# Backplane_Reference_R2_0.net
KiCad netlist of a schematic drawn in EAGLE
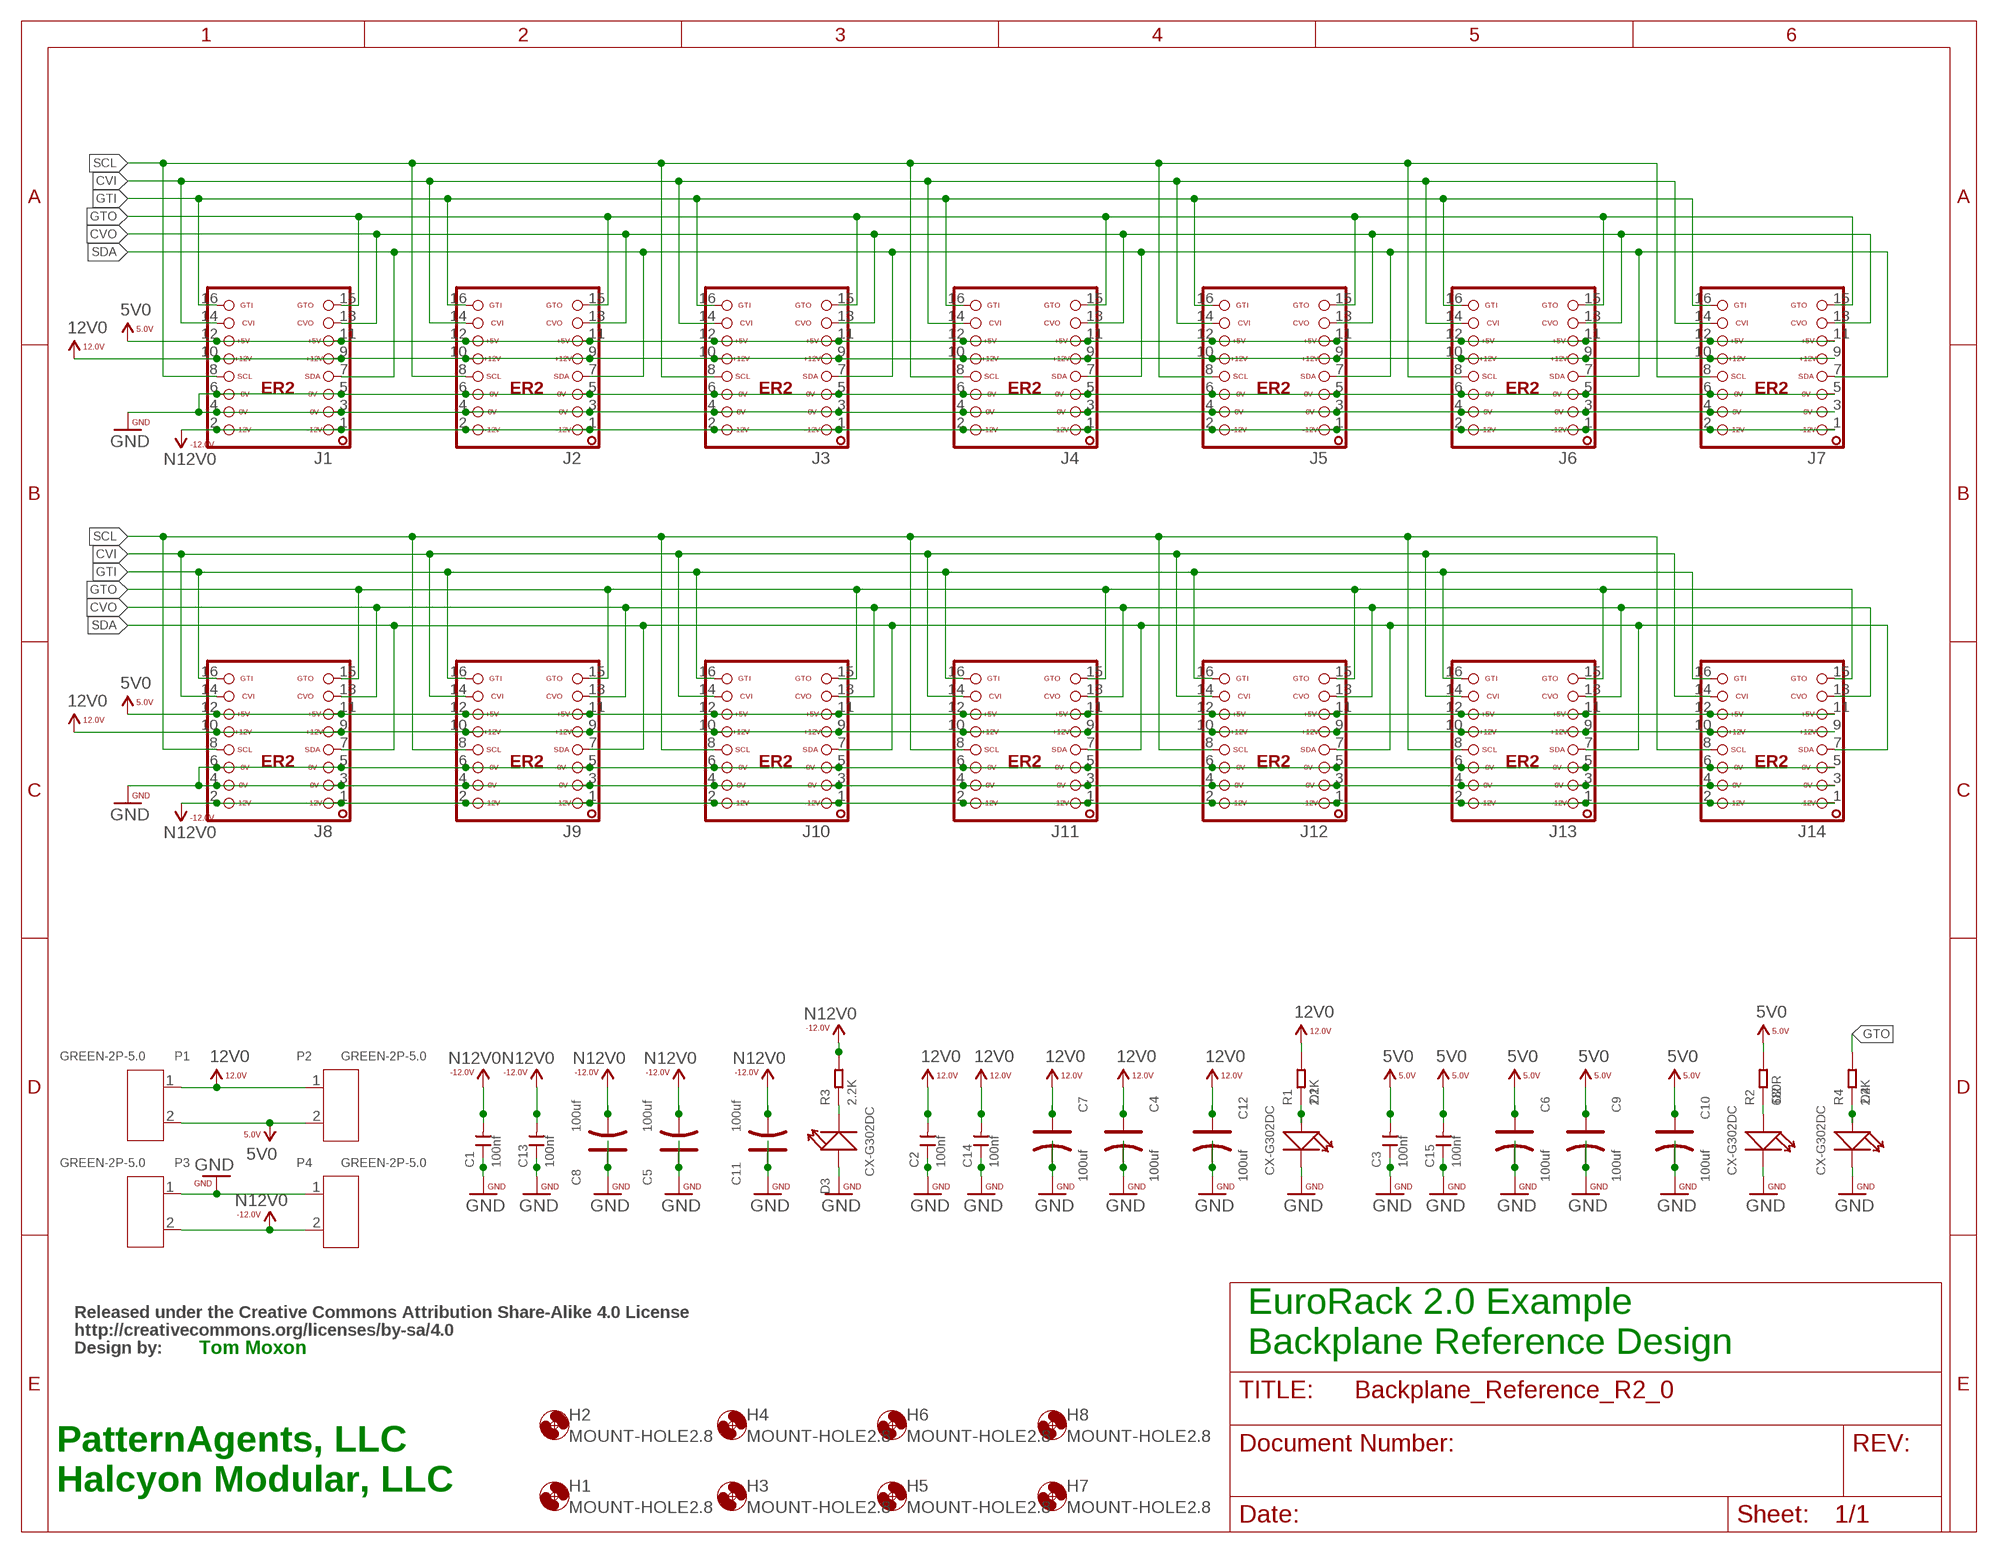
[diagram p0: schematic, sheet 1]

(export (version "E")
  (design (tool "Eeschema 10.0.6"))
  (components
    (comp (ref "C1")
      (value "100nf")
      (footprint "eagle-import:CERAMIC-2.54")
      (fields (field (name "MPN") "CC1-F5SL2A101KSPW"))
      (libsource (lib "eagle-import") (part "DIP-CERAMIC-DISC-100NF-50V-Y5V(D5.0MM)"))
    )
    (comp (ref "C2")
      (value "100nf")
      (footprint "eagle-import:CERAMIC-2.54")
      (fields (field (name "MPN") "CC1-F5SL2A101KSPW"))
      (libsource (lib "eagle-import") (part "DIP-CERAMIC-DISC-100NF-50V-Y5V(D5.0MM)"))
    )
    (comp (ref "C3")
      (value "100nf")
      (footprint "eagle-import:CERAMIC-2.54")
      (fields (field (name "MPN") "CC1-F5SL2A101KSPW"))
      (libsource (lib "eagle-import") (part "DIP-CERAMIC-DISC-100NF-50V-Y5V(D5.0MM)"))
    )
    (comp (ref "C4")
      (value "100uf")
      (footprint "eagle-import:PC-D5.3MM")
      (fields (field (name "MPN") "KS 100uF/16V"))
      (libsource (lib "eagle-import") (part "DIP-ALUMINUM-100UF-16V(D5-H7MM)"))
    )
    (comp (ref "C5")
      (value "100uf")
      (footprint "eagle-import:PC-D5.3MM")
      (fields (field (name "MPN") "KS 100uF/16V"))
      (libsource (lib "eagle-import") (part "DIP-ALUMINUM-100UF-16V(D5-H7MM)"))
    )
    (comp (ref "C6")
      (value "100uf")
      (footprint "eagle-import:PC-D5.3MM")
      (fields (field (name "MPN") "KS 100uF/16V"))
      (libsource (lib "eagle-import") (part "DIP-ALUMINUM-100UF-16V(D5-H7MM)"))
    )
    (comp (ref "C7")
      (value "100uf")
      (footprint "eagle-import:PC-D5.3MM")
      (fields (field (name "MPN") "KS 100uF/16V"))
      (libsource (lib "eagle-import") (part "DIP-ALUMINUM-100UF-16V(D5-H7MM)"))
    )
    (comp (ref "C8")
      (value "100uf")
      (footprint "eagle-import:PC-D5.3MM")
      (fields (field (name "MPN") "KS 100uF/16V"))
      (libsource (lib "eagle-import") (part "DIP-ALUMINUM-100UF-16V(D5-H7MM)"))
    )
    (comp (ref "C9")
      (value "100uf")
      (footprint "eagle-import:PC-D5.3MM")
      (fields (field (name "MPN") "KS 100uF/16V"))
      (libsource (lib "eagle-import") (part "DIP-ALUMINUM-100UF-16V(D5-H7MM)"))
    )
    (comp (ref "C10")
      (value "100uf")
      (footprint "eagle-import:PC-D5.3MM")
      (fields (field (name "MPN") "KS 100uF/16V"))
      (libsource (lib "eagle-import") (part "DIP-ALUMINUM-100UF-16V(D5-H7MM)"))
    )
    (comp (ref "C11")
      (value "100uf")
      (footprint "eagle-import:PC-D5.3MM")
      (fields (field (name "MPN") "KS 100uF/16V"))
      (libsource (lib "eagle-import") (part "DIP-ALUMINUM-100UF-16V(D5-H7MM)"))
    )
    (comp (ref "C12")
      (value "100uf")
      (footprint "eagle-import:PC-D5.3MM")
      (fields (field (name "MPN") "KS 100uF/16V"))
      (libsource (lib "eagle-import") (part "DIP-ALUMINUM-100UF-16V(D5-H7MM)"))
    )
    (comp (ref "C13")
      (value "100nf")
      (footprint "eagle-import:CERAMIC-2.54")
      (fields (field (name "MPN") "CC1-F5SL2A101KSPW"))
      (libsource (lib "eagle-import") (part "DIP-CERAMIC-DISC-100NF-50V-Y5V(D5.0MM)"))
    )
    (comp (ref "C14")
      (value "100nf")
      (footprint "eagle-import:CERAMIC-2.54")
      (fields (field (name "MPN") "CC1-F5SL2A101KSPW"))
      (libsource (lib "eagle-import") (part "DIP-CERAMIC-DISC-100NF-50V-Y5V(D5.0MM)"))
    )
    (comp (ref "C15")
      (value "100nf")
      (footprint "eagle-import:CERAMIC-2.54")
      (fields (field (name "MPN") "CC1-F5SL2A101KSPW"))
      (libsource (lib "eagle-import") (part "DIP-CERAMIC-DISC-100NF-50V-Y5V(D5.0MM)"))
    )
    (comp (ref "D1")
      (value "CX-G302DC")
      (footprint "eagle-import:LED2-2.54-D3.0MM")
      (libsource (lib "eagle-import") (part "DIP-LED-GREEN-GREEN(2P-D3MM)"))
    )
    (comp (ref "D2")
      (value "CX-G302DC")
      (footprint "eagle-import:LED2-2.54-D3.0MM")
      (libsource (lib "eagle-import") (part "DIP-LED-GREEN-GREEN(2P-D3MM)"))
    )
    (comp (ref "D3")
      (value "CX-G302DC")
      (footprint "eagle-import:LED2-2.54-D3.0MM")
      (libsource (lib "eagle-import") (part "DIP-LED-GREEN-GREEN(2P-D3MM)"))
    )
    (comp (ref "D4")
      (value "CX-G302DC")
      (footprint "eagle-import:LED2-2.54-D3.0MM")
      (libsource (lib "eagle-import") (part "DIP-LED-GREEN-GREEN(2P-D3MM)"))
    )
    (comp (ref "H1")
      (value "MOUNT-HOLE2.8")
      (footprint "eagle-import:2,8")
      (libsource (lib "eagle-import") (part "MOUNT-HOLE2.8"))
    )
    (comp (ref "H2")
      (value "MOUNT-HOLE2.8")
      (footprint "eagle-import:2,8")
      (libsource (lib "eagle-import") (part "MOUNT-HOLE2.8"))
    )
    (comp (ref "H3")
      (value "MOUNT-HOLE2.8")
      (footprint "eagle-import:2,8")
      (libsource (lib "eagle-import") (part "MOUNT-HOLE2.8"))
    )
    (comp (ref "H4")
      (value "MOUNT-HOLE2.8")
      (footprint "eagle-import:2,8")
      (libsource (lib "eagle-import") (part "MOUNT-HOLE2.8"))
    )
    (comp (ref "H5")
      (value "MOUNT-HOLE2.8")
      (footprint "eagle-import:2,8")
      (libsource (lib "eagle-import") (part "MOUNT-HOLE2.8"))
    )
    (comp (ref "H6")
      (value "MOUNT-HOLE2.8")
      (footprint "eagle-import:2,8")
      (libsource (lib "eagle-import") (part "MOUNT-HOLE2.8"))
    )
    (comp (ref "H7")
      (value "MOUNT-HOLE2.8")
      (footprint "eagle-import:2,8")
      (libsource (lib "eagle-import") (part "MOUNT-HOLE2.8"))
    )
    (comp (ref "H8")
      (value "MOUNT-HOLE2.8")
      (footprint "eagle-import:2,8")
      (libsource (lib "eagle-import") (part "MOUNT-HOLE2.8"))
    )
    (comp (ref "J1")
      (value "ER2-SHROUD")
      (footprint "eagle-import:ER2")
      (libsource (lib "eagle-import") (part "ER2-SHROUD"))
    )
    (comp (ref "J2")
      (value "ER2-SHROUD")
      (footprint "eagle-import:ER2")
      (libsource (lib "eagle-import") (part "ER2-SHROUD"))
    )
    (comp (ref "J3")
      (value "ER2-SHROUD")
      (footprint "eagle-import:ER2")
      (libsource (lib "eagle-import") (part "ER2-SHROUD"))
    )
    (comp (ref "J4")
      (value "ER2-SHROUD")
      (footprint "eagle-import:ER2")
      (libsource (lib "eagle-import") (part "ER2-SHROUD"))
    )
    (comp (ref "J5")
      (value "ER2-SHROUD")
      (footprint "eagle-import:ER2")
      (libsource (lib "eagle-import") (part "ER2-SHROUD"))
    )
    (comp (ref "J6")
      (value "ER2-SHROUD")
      (footprint "eagle-import:ER2")
      (libsource (lib "eagle-import") (part "ER2-SHROUD"))
    )
    (comp (ref "J7")
      (value "ER2-SHROUD")
      (footprint "eagle-import:ER2")
      (libsource (lib "eagle-import") (part "ER2-SHROUD"))
    )
    (comp (ref "J8")
      (value "ER2-SHROUD")
      (footprint "eagle-import:ER2")
      (libsource (lib "eagle-import") (part "ER2-SHROUD"))
    )
    (comp (ref "J9")
      (value "ER2-SHROUD")
      (footprint "eagle-import:ER2")
      (libsource (lib "eagle-import") (part "ER2-SHROUD"))
    )
    (comp (ref "J10")
      (value "ER2-SHROUD")
      (footprint "eagle-import:ER2")
      (libsource (lib "eagle-import") (part "ER2-SHROUD"))
    )
    (comp (ref "J11")
      (value "ER2-SHROUD")
      (footprint "eagle-import:ER2")
      (libsource (lib "eagle-import") (part "ER2-SHROUD"))
    )
    (comp (ref "J12")
      (value "ER2-SHROUD")
      (footprint "eagle-import:ER2")
      (libsource (lib "eagle-import") (part "ER2-SHROUD"))
    )
    (comp (ref "J13")
      (value "ER2-SHROUD")
      (footprint "eagle-import:ER2")
      (libsource (lib "eagle-import") (part "ER2-SHROUD"))
    )
    (comp (ref "J14")
      (value "ER2-SHROUD")
      (footprint "eagle-import:ER2")
      (libsource (lib "eagle-import") (part "ER2-SHROUD"))
    )
    (comp (ref "P1")
      (value "GREEN-2P-5.0")
      (footprint "eagle-import:H2-5.0-10.5X8.0MM")
      (libsource (lib "eagle-import") (part "SCREW-TERMINAL-GREEN(2P-5.0)"))
    )
    (comp (ref "P2")
      (value "GREEN-2P-5.0")
      (footprint "eagle-import:H2-5.0-10.5X8.0MM")
      (libsource (lib "eagle-import") (part "SCREW-TERMINAL-GREEN(2P-5.0)"))
    )
    (comp (ref "P3")
      (value "GREEN-2P-5.0")
      (footprint "eagle-import:H2-5.0-10.5X8.0MM")
      (libsource (lib "eagle-import") (part "SCREW-TERMINAL-GREEN(2P-5.0)"))
    )
    (comp (ref "P4")
      (value "GREEN-2P-5.0")
      (footprint "eagle-import:H2-5.0-10.5X8.0MM")
      (libsource (lib "eagle-import") (part "SCREW-TERMINAL-GREEN(2P-5.0)"))
    )
    (comp (ref "R1")
      (value "2.2K")
      (footprint "eagle-import:PR-D2.3XL6.5MM")
      (fields (field (name "MPN") "FHCFR-1/4W-222J"))
      (libsource (lib "eagle-import") (part "DIP-RES-2.2K-5%-1/4W(PR-D2.3XL6.5MM)"))
    )
    (comp (ref "R2")
      (value "680R")
      (footprint "eagle-import:PR-D2.3XL6.5MM")
      (fields (field (name "MPN") "FHCFR-1/4W-681J"))
      (libsource (lib "eagle-import") (part "DIP-RES-680R-5%-1/4W(PR-D2.3XL6.5MM)"))
    )
    (comp (ref "R3")
      (value "2.2K")
      (footprint "eagle-import:PR-D2.3XL6.5MM")
      (fields (field (name "MPN") "FHCFR-1/4W-222J"))
      (libsource (lib "eagle-import") (part "DIP-RES-2.2K-5%-1/4W(PR-D2.3XL6.5MM)"))
    )
    (comp (ref "R4")
      (value "2.2K")
      (footprint "eagle-import:PR-D2.3XL6.5MM")
      (fields (field (name "MPN") "FHCFR-1/4W-222J"))
      (libsource (lib "eagle-import") (part "DIP-RES-2.2K-5%-1/4W(PR-D2.3XL6.5MM)"))
    )
    (comp (ref "U$48")
      (value "BY_CC_SA_TEXTTEXT")
      (footprint "eagle-import:BY_CC_SA_TEXT")
      (libsource (lib "eagle-import") (part "BY_CC_SA_TEXTTEXT"))
    )
  )
  (nets
    (net (code "1") (name "5V0") (class "Default")
      (node (ref "C10") (pin "+") (pinfunction "+_+") (pintype "passive"))
      (node (ref "C15") (pin "2") (pinfunction "2_2") (pintype "passive"))
      (node (ref "C3") (pin "2") (pinfunction "2_2") (pintype "passive"))
      (node (ref "C6") (pin "+") (pinfunction "+_+") (pintype "passive"))
      (node (ref "C9") (pin "+") (pinfunction "+_+") (pintype "passive"))
      (node (ref "J1") (pin "11") (pinfunction "11_11") (pintype "passive"))
      (node (ref "J1") (pin "12") (pinfunction "12_12") (pintype "passive"))
      (node (ref "J10") (pin "11") (pinfunction "11_11") (pintype "passive"))
      (node (ref "J10") (pin "12") (pinfunction "12_12") (pintype "passive"))
      (node (ref "J11") (pin "11") (pinfunction "11_11") (pintype "passive"))
      (node (ref "J11") (pin "12") (pinfunction "12_12") (pintype "passive"))
      (node (ref "J12") (pin "11") (pinfunction "11_11") (pintype "passive"))
      (node (ref "J12") (pin "12") (pinfunction "12_12") (pintype "passive"))
      (node (ref "J13") (pin "11") (pinfunction "11_11") (pintype "passive"))
      (node (ref "J13") (pin "12") (pinfunction "12_12") (pintype "passive"))
      (node (ref "J14") (pin "11") (pinfunction "11_11") (pintype "passive"))
      (node (ref "J14") (pin "12") (pinfunction "12_12") (pintype "passive"))
      (node (ref "J2") (pin "11") (pinfunction "11_11") (pintype "passive"))
      (node (ref "J2") (pin "12") (pinfunction "12_12") (pintype "passive"))
      (node (ref "J3") (pin "11") (pinfunction "11_11") (pintype "passive"))
      (node (ref "J3") (pin "12") (pinfunction "12_12") (pintype "passive"))
      (node (ref "J4") (pin "11") (pinfunction "11_11") (pintype "passive"))
      (node (ref "J4") (pin "12") (pinfunction "12_12") (pintype "passive"))
      (node (ref "J5") (pin "11") (pinfunction "11_11") (pintype "passive"))
      (node (ref "J5") (pin "12") (pinfunction "12_12") (pintype "passive"))
      (node (ref "J6") (pin "11") (pinfunction "11_11") (pintype "passive"))
      (node (ref "J6") (pin "12") (pinfunction "12_12") (pintype "passive"))
      (node (ref "J7") (pin "11") (pinfunction "11_11") (pintype "passive"))
      (node (ref "J7") (pin "12") (pinfunction "12_12") (pintype "passive"))
      (node (ref "J8") (pin "11") (pinfunction "11_11") (pintype "passive"))
      (node (ref "J8") (pin "12") (pinfunction "12_12") (pintype "passive"))
      (node (ref "J9") (pin "11") (pinfunction "11_11") (pintype "passive"))
      (node (ref "J9") (pin "12") (pinfunction "12_12") (pintype "passive"))
      (node (ref "P1") (pin "2") (pinfunction "2_2") (pintype "bidirectional"))
      (node (ref "P2") (pin "2") (pinfunction "2_2") (pintype "bidirectional"))
      (node (ref "R2") (pin "2") (pinfunction "2_2") (pintype "passive"))
    )
    (net (code "2") (name "12V0") (class "Default")
      (node (ref "C12") (pin "+") (pinfunction "+_+") (pintype "passive"))
      (node (ref "C14") (pin "2") (pinfunction "2_2") (pintype "passive"))
      (node (ref "C2") (pin "2") (pinfunction "2_2") (pintype "passive"))
      (node (ref "C4") (pin "+") (pinfunction "+_+") (pintype "passive"))
      (node (ref "C7") (pin "+") (pinfunction "+_+") (pintype "passive"))
      (node (ref "J1") (pin "10") (pinfunction "10_10") (pintype "passive"))
      (node (ref "J1") (pin "9") (pinfunction "9_9") (pintype "passive"))
      (node (ref "J10") (pin "10") (pinfunction "10_10") (pintype "passive"))
      (node (ref "J10") (pin "9") (pinfunction "9_9") (pintype "passive"))
      (node (ref "J11") (pin "10") (pinfunction "10_10") (pintype "passive"))
      (node (ref "J11") (pin "9") (pinfunction "9_9") (pintype "passive"))
      (node (ref "J12") (pin "10") (pinfunction "10_10") (pintype "passive"))
      (node (ref "J12") (pin "9") (pinfunction "9_9") (pintype "passive"))
      (node (ref "J13") (pin "10") (pinfunction "10_10") (pintype "passive"))
      (node (ref "J13") (pin "9") (pinfunction "9_9") (pintype "passive"))
      (node (ref "J14") (pin "10") (pinfunction "10_10") (pintype "passive"))
      (node (ref "J14") (pin "9") (pinfunction "9_9") (pintype "passive"))
      (node (ref "J2") (pin "10") (pinfunction "10_10") (pintype "passive"))
      (node (ref "J2") (pin "9") (pinfunction "9_9") (pintype "passive"))
      (node (ref "J3") (pin "10") (pinfunction "10_10") (pintype "passive"))
      (node (ref "J3") (pin "9") (pinfunction "9_9") (pintype "passive"))
      (node (ref "J4") (pin "10") (pinfunction "10_10") (pintype "passive"))
      (node (ref "J4") (pin "9") (pinfunction "9_9") (pintype "passive"))
      (node (ref "J5") (pin "10") (pinfunction "10_10") (pintype "passive"))
      (node (ref "J5") (pin "9") (pinfunction "9_9") (pintype "passive"))
      (node (ref "J6") (pin "10") (pinfunction "10_10") (pintype "passive"))
      (node (ref "J6") (pin "9") (pinfunction "9_9") (pintype "passive"))
      (node (ref "J7") (pin "10") (pinfunction "10_10") (pintype "passive"))
      (node (ref "J7") (pin "9") (pinfunction "9_9") (pintype "passive"))
      (node (ref "J8") (pin "10") (pinfunction "10_10") (pintype "passive"))
      (node (ref "J8") (pin "9") (pinfunction "9_9") (pintype "passive"))
      (node (ref "J9") (pin "10") (pinfunction "10_10") (pintype "passive"))
      (node (ref "J9") (pin "9") (pinfunction "9_9") (pintype "passive"))
      (node (ref "P1") (pin "1") (pinfunction "1_1") (pintype "bidirectional"))
      (node (ref "P2") (pin "1") (pinfunction "1_1") (pintype "bidirectional"))
      (node (ref "R1") (pin "2") (pinfunction "2_2") (pintype "passive"))
    )
    (net (code "3") (name "CVI") (class "Default")
      (node (ref "J1") (pin "14") (pinfunction "14_14") (pintype "passive"))
      (node (ref "J10") (pin "14") (pinfunction "14_14") (pintype "passive"))
      (node (ref "J11") (pin "14") (pinfunction "14_14") (pintype "passive"))
      (node (ref "J12") (pin "14") (pinfunction "14_14") (pintype "passive"))
      (node (ref "J13") (pin "14") (pinfunction "14_14") (pintype "passive"))
      (node (ref "J14") (pin "14") (pinfunction "14_14") (pintype "passive"))
      (node (ref "J2") (pin "14") (pinfunction "14_14") (pintype "passive"))
      (node (ref "J3") (pin "14") (pinfunction "14_14") (pintype "passive"))
      (node (ref "J4") (pin "14") (pinfunction "14_14") (pintype "passive"))
      (node (ref "J5") (pin "14") (pinfunction "14_14") (pintype "passive"))
      (node (ref "J6") (pin "14") (pinfunction "14_14") (pintype "passive"))
      (node (ref "J7") (pin "14") (pinfunction "14_14") (pintype "passive"))
      (node (ref "J8") (pin "14") (pinfunction "14_14") (pintype "passive"))
      (node (ref "J9") (pin "14") (pinfunction "14_14") (pintype "passive"))
    )
    (net (code "4") (name "CVO") (class "Default")
      (node (ref "J1") (pin "13") (pinfunction "13_13") (pintype "passive"))
      (node (ref "J10") (pin "13") (pinfunction "13_13") (pintype "passive"))
      (node (ref "J11") (pin "13") (pinfunction "13_13") (pintype "passive"))
      (node (ref "J12") (pin "13") (pinfunction "13_13") (pintype "passive"))
      (node (ref "J13") (pin "13") (pinfunction "13_13") (pintype "passive"))
      (node (ref "J14") (pin "13") (pinfunction "13_13") (pintype "passive"))
      (node (ref "J2") (pin "13") (pinfunction "13_13") (pintype "passive"))
      (node (ref "J3") (pin "13") (pinfunction "13_13") (pintype "passive"))
      (node (ref "J4") (pin "13") (pinfunction "13_13") (pintype "passive"))
      (node (ref "J5") (pin "13") (pinfunction "13_13") (pintype "passive"))
      (node (ref "J6") (pin "13") (pinfunction "13_13") (pintype "passive"))
      (node (ref "J7") (pin "13") (pinfunction "13_13") (pintype "passive"))
      (node (ref "J8") (pin "13") (pinfunction "13_13") (pintype "passive"))
      (node (ref "J9") (pin "13") (pinfunction "13_13") (pintype "passive"))
    )
    (net (code "5") (name "GND") (class "Default")
      (node (ref "C1") (pin "1") (pinfunction "1_1") (pintype "passive"))
      (node (ref "C10") (pin "-") (pinfunction "-_-") (pintype "passive"))
      (node (ref "C11") (pin "+") (pinfunction "+_+") (pintype "passive"))
      (node (ref "C12") (pin "-") (pinfunction "-_-") (pintype "passive"))
      (node (ref "C13") (pin "1") (pinfunction "1_1") (pintype "passive"))
      (node (ref "C14") (pin "1") (pinfunction "1_1") (pintype "passive"))
      (node (ref "C15") (pin "1") (pinfunction "1_1") (pintype "passive"))
      (node (ref "C2") (pin "1") (pinfunction "1_1") (pintype "passive"))
      (node (ref "C3") (pin "1") (pinfunction "1_1") (pintype "passive"))
      (node (ref "C4") (pin "-") (pinfunction "-_-") (pintype "passive"))
      (node (ref "C5") (pin "+") (pinfunction "+_+") (pintype "passive"))
      (node (ref "C6") (pin "-") (pinfunction "-_-") (pintype "passive"))
      (node (ref "C7") (pin "-") (pinfunction "-_-") (pintype "passive"))
      (node (ref "C8") (pin "+") (pinfunction "+_+") (pintype "passive"))
      (node (ref "C9") (pin "-") (pinfunction "-_-") (pintype "passive"))
      (node (ref "D1") (pin "K") (pinfunction "-_K") (pintype "passive"))
      (node (ref "D2") (pin "K") (pinfunction "-_K") (pintype "passive"))
      (node (ref "D3") (pin "A") (pinfunction "+_A") (pintype "passive"))
      (node (ref "D4") (pin "K") (pinfunction "-_K") (pintype "passive"))
      (node (ref "J1") (pin "3") (pinfunction "3_3") (pintype "passive"))
      (node (ref "J1") (pin "4") (pinfunction "4_4") (pintype "passive"))
      (node (ref "J1") (pin "5") (pinfunction "5_5") (pintype "passive"))
      (node (ref "J1") (pin "6") (pinfunction "6_6") (pintype "passive"))
      (node (ref "J10") (pin "3") (pinfunction "3_3") (pintype "passive"))
      (node (ref "J10") (pin "4") (pinfunction "4_4") (pintype "passive"))
      (node (ref "J10") (pin "5") (pinfunction "5_5") (pintype "passive"))
      (node (ref "J10") (pin "6") (pinfunction "6_6") (pintype "passive"))
      (node (ref "J11") (pin "3") (pinfunction "3_3") (pintype "passive"))
      (node (ref "J11") (pin "4") (pinfunction "4_4") (pintype "passive"))
      (node (ref "J11") (pin "5") (pinfunction "5_5") (pintype "passive"))
      (node (ref "J11") (pin "6") (pinfunction "6_6") (pintype "passive"))
      (node (ref "J12") (pin "3") (pinfunction "3_3") (pintype "passive"))
      (node (ref "J12") (pin "4") (pinfunction "4_4") (pintype "passive"))
      (node (ref "J12") (pin "5") (pinfunction "5_5") (pintype "passive"))
      (node (ref "J12") (pin "6") (pinfunction "6_6") (pintype "passive"))
      (node (ref "J13") (pin "3") (pinfunction "3_3") (pintype "passive"))
      (node (ref "J13") (pin "4") (pinfunction "4_4") (pintype "passive"))
      (node (ref "J13") (pin "5") (pinfunction "5_5") (pintype "passive"))
      (node (ref "J13") (pin "6") (pinfunction "6_6") (pintype "passive"))
      (node (ref "J14") (pin "3") (pinfunction "3_3") (pintype "passive"))
      (node (ref "J14") (pin "4") (pinfunction "4_4") (pintype "passive"))
      (node (ref "J14") (pin "5") (pinfunction "5_5") (pintype "passive"))
      (node (ref "J14") (pin "6") (pinfunction "6_6") (pintype "passive"))
      (node (ref "J2") (pin "3") (pinfunction "3_3") (pintype "passive"))
      (node (ref "J2") (pin "4") (pinfunction "4_4") (pintype "passive"))
      (node (ref "J2") (pin "5") (pinfunction "5_5") (pintype "passive"))
      (node (ref "J2") (pin "6") (pinfunction "6_6") (pintype "passive"))
      (node (ref "J3") (pin "3") (pinfunction "3_3") (pintype "passive"))
      (node (ref "J3") (pin "4") (pinfunction "4_4") (pintype "passive"))
      (node (ref "J3") (pin "5") (pinfunction "5_5") (pintype "passive"))
      (node (ref "J3") (pin "6") (pinfunction "6_6") (pintype "passive"))
      (node (ref "J4") (pin "3") (pinfunction "3_3") (pintype "passive"))
      (node (ref "J4") (pin "4") (pinfunction "4_4") (pintype "passive"))
      (node (ref "J4") (pin "5") (pinfunction "5_5") (pintype "passive"))
      (node (ref "J4") (pin "6") (pinfunction "6_6") (pintype "passive"))
      (node (ref "J5") (pin "3") (pinfunction "3_3") (pintype "passive"))
      (node (ref "J5") (pin "4") (pinfunction "4_4") (pintype "passive"))
      (node (ref "J5") (pin "5") (pinfunction "5_5") (pintype "passive"))
      (node (ref "J5") (pin "6") (pinfunction "6_6") (pintype "passive"))
      (node (ref "J6") (pin "3") (pinfunction "3_3") (pintype "passive"))
      (node (ref "J6") (pin "4") (pinfunction "4_4") (pintype "passive"))
      (node (ref "J6") (pin "5") (pinfunction "5_5") (pintype "passive"))
      (node (ref "J6") (pin "6") (pinfunction "6_6") (pintype "passive"))
      (node (ref "J7") (pin "3") (pinfunction "3_3") (pintype "passive"))
      (node (ref "J7") (pin "4") (pinfunction "4_4") (pintype "passive"))
      (node (ref "J7") (pin "5") (pinfunction "5_5") (pintype "passive"))
      (node (ref "J7") (pin "6") (pinfunction "6_6") (pintype "passive"))
      (node (ref "J8") (pin "3") (pinfunction "3_3") (pintype "passive"))
      (node (ref "J8") (pin "4") (pinfunction "4_4") (pintype "passive"))
      (node (ref "J8") (pin "5") (pinfunction "5_5") (pintype "passive"))
      (node (ref "J8") (pin "6") (pinfunction "6_6") (pintype "passive"))
      (node (ref "J9") (pin "3") (pinfunction "3_3") (pintype "passive"))
      (node (ref "J9") (pin "4") (pinfunction "4_4") (pintype "passive"))
      (node (ref "J9") (pin "5") (pinfunction "5_5") (pintype "passive"))
      (node (ref "J9") (pin "6") (pinfunction "6_6") (pintype "passive"))
      (node (ref "P3") (pin "1") (pinfunction "1_1") (pintype "bidirectional"))
      (node (ref "P4") (pin "1") (pinfunction "1_1") (pintype "bidirectional"))
    )
    (net (code "6") (name "GTI") (class "Default")
      (node (ref "J1") (pin "16") (pinfunction "16_16") (pintype "passive"))
      (node (ref "J10") (pin "16") (pinfunction "16_16") (pintype "passive"))
      (node (ref "J11") (pin "16") (pinfunction "16_16") (pintype "passive"))
      (node (ref "J12") (pin "16") (pinfunction "16_16") (pintype "passive"))
      (node (ref "J13") (pin "16") (pinfunction "16_16") (pintype "passive"))
      (node (ref "J14") (pin "16") (pinfunction "16_16") (pintype "passive"))
      (node (ref "J2") (pin "16") (pinfunction "16_16") (pintype "passive"))
      (node (ref "J3") (pin "16") (pinfunction "16_16") (pintype "passive"))
      (node (ref "J4") (pin "16") (pinfunction "16_16") (pintype "passive"))
      (node (ref "J5") (pin "16") (pinfunction "16_16") (pintype "passive"))
      (node (ref "J6") (pin "16") (pinfunction "16_16") (pintype "passive"))
      (node (ref "J7") (pin "16") (pinfunction "16_16") (pintype "passive"))
      (node (ref "J8") (pin "16") (pinfunction "16_16") (pintype "passive"))
      (node (ref "J9") (pin "16") (pinfunction "16_16") (pintype "passive"))
    )
    (net (code "7") (name "GTO") (class "Default")
      (node (ref "J1") (pin "15") (pinfunction "15_15") (pintype "passive"))
      (node (ref "J10") (pin "15") (pinfunction "15_15") (pintype "passive"))
      (node (ref "J11") (pin "15") (pinfunction "15_15") (pintype "passive"))
      (node (ref "J12") (pin "15") (pinfunction "15_15") (pintype "passive"))
      (node (ref "J13") (pin "15") (pinfunction "15_15") (pintype "passive"))
      (node (ref "J14") (pin "15") (pinfunction "15_15") (pintype "passive"))
      (node (ref "J2") (pin "15") (pinfunction "15_15") (pintype "passive"))
      (node (ref "J3") (pin "15") (pinfunction "15_15") (pintype "passive"))
      (node (ref "J4") (pin "15") (pinfunction "15_15") (pintype "passive"))
      (node (ref "J5") (pin "15") (pinfunction "15_15") (pintype "passive"))
      (node (ref "J6") (pin "15") (pinfunction "15_15") (pintype "passive"))
      (node (ref "J7") (pin "15") (pinfunction "15_15") (pintype "passive"))
      (node (ref "J8") (pin "15") (pinfunction "15_15") (pintype "passive"))
      (node (ref "J9") (pin "15") (pinfunction "15_15") (pintype "passive"))
      (node (ref "R4") (pin "2") (pinfunction "2_2") (pintype "passive"))
    )
    (net (code "8") (name "N12V0") (class "Default")
      (node (ref "C1") (pin "2") (pinfunction "2_2") (pintype "passive"))
      (node (ref "C11") (pin "-") (pinfunction "-_-") (pintype "passive"))
      (node (ref "C13") (pin "2") (pinfunction "2_2") (pintype "passive"))
      (node (ref "C5") (pin "-") (pinfunction "-_-") (pintype "passive"))
      (node (ref "C8") (pin "-") (pinfunction "-_-") (pintype "passive"))
      (node (ref "J1") (pin "1") (pinfunction "1_1") (pintype "passive"))
      (node (ref "J1") (pin "2") (pinfunction "2_2") (pintype "passive"))
      (node (ref "J10") (pin "1") (pinfunction "1_1") (pintype "passive"))
      (node (ref "J10") (pin "2") (pinfunction "2_2") (pintype "passive"))
      (node (ref "J11") (pin "1") (pinfunction "1_1") (pintype "passive"))
      (node (ref "J11") (pin "2") (pinfunction "2_2") (pintype "passive"))
      (node (ref "J12") (pin "1") (pinfunction "1_1") (pintype "passive"))
      (node (ref "J12") (pin "2") (pinfunction "2_2") (pintype "passive"))
      (node (ref "J13") (pin "1") (pinfunction "1_1") (pintype "passive"))
      (node (ref "J13") (pin "2") (pinfunction "2_2") (pintype "passive"))
      (node (ref "J14") (pin "1") (pinfunction "1_1") (pintype "passive"))
      (node (ref "J14") (pin "2") (pinfunction "2_2") (pintype "passive"))
      (node (ref "J2") (pin "1") (pinfunction "1_1") (pintype "passive"))
      (node (ref "J2") (pin "2") (pinfunction "2_2") (pintype "passive"))
      (node (ref "J3") (pin "1") (pinfunction "1_1") (pintype "passive"))
      (node (ref "J3") (pin "2") (pinfunction "2_2") (pintype "passive"))
      (node (ref "J4") (pin "1") (pinfunction "1_1") (pintype "passive"))
      (node (ref "J4") (pin "2") (pinfunction "2_2") (pintype "passive"))
      (node (ref "J5") (pin "1") (pinfunction "1_1") (pintype "passive"))
      (node (ref "J5") (pin "2") (pinfunction "2_2") (pintype "passive"))
      (node (ref "J6") (pin "1") (pinfunction "1_1") (pintype "passive"))
      (node (ref "J6") (pin "2") (pinfunction "2_2") (pintype "passive"))
      (node (ref "J7") (pin "1") (pinfunction "1_1") (pintype "passive"))
      (node (ref "J7") (pin "2") (pinfunction "2_2") (pintype "passive"))
      (node (ref "J8") (pin "1") (pinfunction "1_1") (pintype "passive"))
      (node (ref "J8") (pin "2") (pinfunction "2_2") (pintype "passive"))
      (node (ref "J9") (pin "1") (pinfunction "1_1") (pintype "passive"))
      (node (ref "J9") (pin "2") (pinfunction "2_2") (pintype "passive"))
      (node (ref "P3") (pin "2") (pinfunction "2_2") (pintype "bidirectional"))
      (node (ref "P4") (pin "2") (pinfunction "2_2") (pintype "bidirectional"))
      (node (ref "R3") (pin "2") (pinfunction "2_2") (pintype "passive"))
    )
    (net (code "9") (name "Net-(D1-+)") (class "Default")
      (node (ref "D1") (pin "A") (pinfunction "+_A") (pintype "passive"))
      (node (ref "R1") (pin "1") (pinfunction "1_1") (pintype "passive"))
    )
    (net (code "10") (name "Net-(D2-+)") (class "Default")
      (node (ref "D2") (pin "A") (pinfunction "+_A") (pintype "passive"))
      (node (ref "R2") (pin "1") (pinfunction "1_1") (pintype "passive"))
    )
    (net (code "11") (name "Net-(D3--)") (class "Default")
      (node (ref "D3") (pin "K") (pinfunction "-_K") (pintype "passive"))
      (node (ref "R3") (pin "1") (pinfunction "1_1") (pintype "passive"))
    )
    (net (code "12") (name "Net-(D4-+)") (class "Default")
      (node (ref "D4") (pin "A") (pinfunction "+_A") (pintype "passive"))
      (node (ref "R4") (pin "1") (pinfunction "1_1") (pintype "passive"))
    )
    (net (code "13") (name "SCL") (class "Default")
      (node (ref "J1") (pin "8") (pinfunction "8_8") (pintype "passive"))
      (node (ref "J10") (pin "8") (pinfunction "8_8") (pintype "passive"))
      (node (ref "J11") (pin "8") (pinfunction "8_8") (pintype "passive"))
      (node (ref "J12") (pin "8") (pinfunction "8_8") (pintype "passive"))
      (node (ref "J13") (pin "8") (pinfunction "8_8") (pintype "passive"))
      (node (ref "J14") (pin "8") (pinfunction "8_8") (pintype "passive"))
      (node (ref "J2") (pin "8") (pinfunction "8_8") (pintype "passive"))
      (node (ref "J3") (pin "8") (pinfunction "8_8") (pintype "passive"))
      (node (ref "J4") (pin "8") (pinfunction "8_8") (pintype "passive"))
      (node (ref "J5") (pin "8") (pinfunction "8_8") (pintype "passive"))
      (node (ref "J6") (pin "8") (pinfunction "8_8") (pintype "passive"))
      (node (ref "J7") (pin "8") (pinfunction "8_8") (pintype "passive"))
      (node (ref "J8") (pin "8") (pinfunction "8_8") (pintype "passive"))
      (node (ref "J9") (pin "8") (pinfunction "8_8") (pintype "passive"))
    )
    (net (code "14") (name "SDA") (class "Default")
      (node (ref "J1") (pin "7") (pinfunction "7_7") (pintype "passive"))
      (node (ref "J10") (pin "7") (pinfunction "7_7") (pintype "passive"))
      (node (ref "J11") (pin "7") (pinfunction "7_7") (pintype "passive"))
      (node (ref "J12") (pin "7") (pinfunction "7_7") (pintype "passive"))
      (node (ref "J13") (pin "7") (pinfunction "7_7") (pintype "passive"))
      (node (ref "J14") (pin "7") (pinfunction "7_7") (pintype "passive"))
      (node (ref "J2") (pin "7") (pinfunction "7_7") (pintype "passive"))
      (node (ref "J3") (pin "7") (pinfunction "7_7") (pintype "passive"))
      (node (ref "J4") (pin "7") (pinfunction "7_7") (pintype "passive"))
      (node (ref "J5") (pin "7") (pinfunction "7_7") (pintype "passive"))
      (node (ref "J6") (pin "7") (pinfunction "7_7") (pintype "passive"))
      (node (ref "J7") (pin "7") (pinfunction "7_7") (pintype "passive"))
      (node (ref "J8") (pin "7") (pinfunction "7_7") (pintype "passive"))
      (node (ref "J9") (pin "7") (pinfunction "7_7") (pintype "passive"))
    )
  )
)
